# Sheet4.net
KiCad netlist of a schematic drawn in Altium Designer
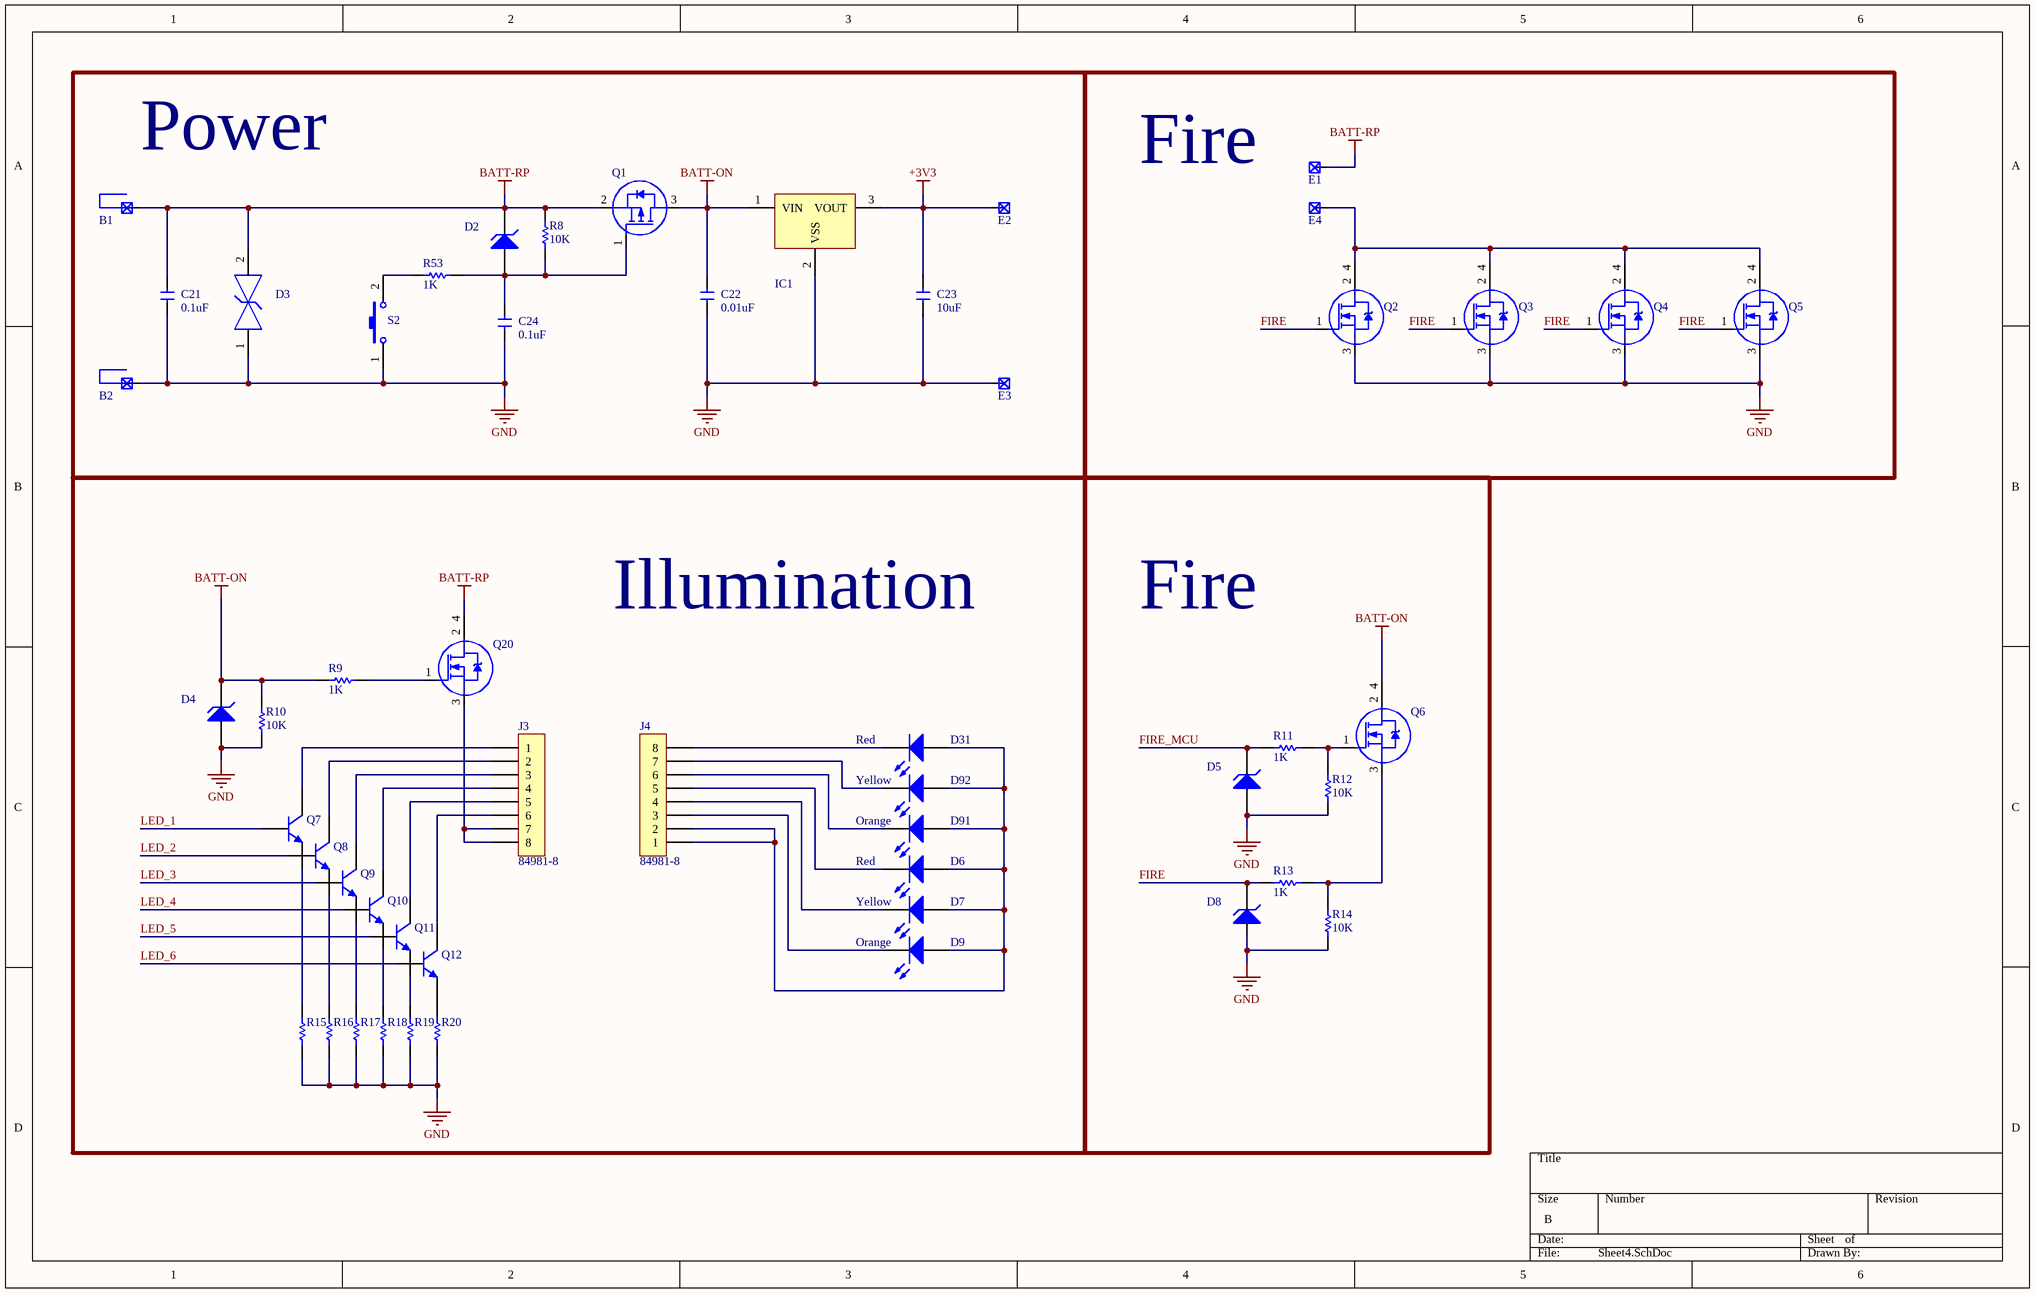
[diagram p0: Sheet4.SchDoc]

(export (version "E")
  (design (tool "Eeschema 10.0.6"))
  (components
    (comp (ref "B1")
      (value "BATT CONTACT")
      (footprint "BATTERY CONTACT KEYSTONE 209")
      (description "BATT_Contact_Keystone_209")
      (fields (field (name "MANUFACTURER") "Keystone Electronics"))
      (libsource (lib "Erico_Ignitor") (part "BATT_Contact_Keystone_209"))
    )
    (comp (ref "B2")
      (value "BATT CONTACT")
      (footprint "BATTERY CONTACT KEYSTONE 209")
      (description "BATT_Contact_Keystone_209")
      (fields (field (name "MANUFACTURER") "Keystone Electronics"))
      (libsource (lib "Erico_Ignitor") (part "BATT_Contact_Keystone_209"))
    )
    (comp (ref "C21")
      (value "0.1uF")
      (footprint "CAPC2012N")
      (description "CAP CER 0.1UF 50V")
      (fields (field (name "MANUFACTURER") "KEMET") (field (name "TOLERANCE") "20%"))
      (libsource (lib "Erico_Ignitor") (part "Cap_0.1uF_50V_0805"))
    )
    (comp (ref "C22")
      (value "0.01uF")
      (footprint "CAPC2012N")
      (description "CAP CER 0.01UF 50V")
      (fields (field (name "MANUFACTURER") "KEMET") (field (name "TOLERANCE") "10%"))
      (libsource (lib "Erico_Ignitor") (part "Cap_0.01uF_50V_0805"))
    )
    (comp (ref "C23")
      (value "10uF")
      (footprint "CAPC2012N")
      (description "CAP CER 10uF 10V 0805")
      (fields (field (name "MANUFACTURER") "TDK") (field (name "TOLERANCE") "10%"))
      (libsource (lib "Erico_Ignitor") (part "Cap_10uF_10V_0805"))
    )
    (comp (ref "C24")
      (value "0.1uF")
      (footprint "CAPC2012N")
      (description "CAP CER 0.1UF 50V")
      (fields (field (name "MANUFACTURER") "KEMET") (field (name "TOLERANCE") "20%"))
      (libsource (lib "Erico_Ignitor") (part "Cap_0.1uF_50V_0805"))
    )
    (comp (ref "D2")
      (value "Diode, Zener, BZX84C18")
      (footprint "SOT23")
      (description "DIODE ZENER 18V 300mW SOT23")
      (fields (field (name "MANUFACTURER") "Diodes") (field (name "TOLERANCE") "6%"))
      (libsource (lib "Erico_Ignitor") (part "Diode_BZX84C18"))
    )
    (comp (ref "D3")
      (value "SMAJ24CA")
      (footprint "FP-SMAJ-CA-MFG")
      (description "TVS DIODE 24V 38.9V DO214AC")
      (fields
        (field (name "MANUFACTURER") "Littelfuse")
        (field (name "OCTOPART") "https://octopart.com/smaj24ca-littelfuse-350011")
      )
      (libsource (lib "Altium Content Vault") (part "876f4347bf90aa6f500f43e3cd03972"))
    )
    (comp (ref "D4")
      (value "Diode, Zener, BZX84C18")
      (footprint "SOT23")
      (description "DIODE ZENER 18V 300mW SOT23")
      (fields (field (name "MANUFACTURER") "Diodes") (field (name "TOLERANCE") "6%"))
      (libsource (lib "Erico_Ignitor") (part "Diode_BZX84C18"))
    )
    (comp (ref "D5")
      (value "Diode, Zener, BZX84C18")
      (footprint "SOT23")
      (description "DIODE ZENER 18V 300mW SOT23")
      (fields (field (name "MANUFACTURER") "Diodes") (field (name "TOLERANCE") "6%"))
      (libsource (lib "Erico_Ignitor") (part "Diode_BZX84C18"))
    )
    (comp (ref "D6")
      (value "LED_RED_0603")
      (footprint "LED_LTST-C190KRKT")
      (description "LED RED 0603 SMD")
      (fields (field (name "MANUFACTURER") "Vishay Lite-On"))
      (libsource (lib "Erico_Ignitor") (part "LED_RED_LTST-C190"))
    )
    (comp (ref "D7")
      (value "LED_YELLOW_LTST-C194KSKT")
      (footprint "LED_LTST-C194KSKT")
      (description "LED YELLOW 0603 SMD")
      (fields (field (name "MANUFACTURER") "Vishay Lite-On"))
      (libsource (lib "Erico_Ignitor") (part "LED_YELLOW_LTST-C194KSKT"))
    )
    (comp (ref "D8")
      (value "Diode, Zener, BZX84C18")
      (footprint "SOT23")
      (description "DIODE ZENER 18V 300mW SOT23")
      (fields (field (name "MANUFACTURER") "Diodes") (field (name "TOLERANCE") "6%"))
      (libsource (lib "Erico_Ignitor") (part "Diode_BZX84C18"))
    )
    (comp (ref "D9")
      (value "LED_ORANGE_0603")
      (footprint "LED_LTST-C190KFKT")
      (description "LED ORANGE 0603 SMD")
      (fields (field (name "MANUFACTURER") "Vishay Lite-On"))
      (libsource (lib "Erico_Ignitor") (part "LED_ORANGE_LTST-C190KFKT"))
    )
    (comp (ref "D31")
      (value "LED_RED_0603")
      (footprint "LED_LTST-C190KRKT")
      (description "LED RED 0603 SMD")
      (fields (field (name "MANUFACTURER") "Vishay Lite-On"))
      (libsource (lib "Erico_Ignitor") (part "LED_RED_LTST-C190"))
    )
    (comp (ref "D91")
      (value "LED_ORANGE_0603")
      (footprint "LED_LTST-C190KFKT")
      (description "LED ORANGE 0603 SMD")
      (fields (field (name "MANUFACTURER") "Vishay Lite-On"))
      (libsource (lib "Erico_Ignitor") (part "LED_ORANGE_LTST-C190KFKT"))
    )
    (comp (ref "D92")
      (value "LED_YELLOW_LTST-C194KSKT")
      (footprint "LED_LTST-C194KSKT")
      (description "LED YELLOW 0603 SMD")
      (fields (field (name "MANUFACTURER") "Vishay Lite-On"))
      (libsource (lib "Erico_Ignitor") (part "LED_YELLOW_LTST-C194KSKT"))
    )
    (comp (ref "E1")
      (value "Testpoint")
      (footprint "Test_point")
      (libsource (lib "Erico_Ignitor") (part "Test Point"))
    )
    (comp (ref "E2") (value "Testpoint") (footprint "Test_point") (libsource (lib "") (part "Test Point_1")))
    (comp (ref "E3") (value "Testpoint") (footprint "Test_point") (libsource (lib "") (part "Test Point_1")))
    (comp (ref "E4")
      (value "Testpoint")
      (footprint "Test_point")
      (libsource (lib "Erico_Ignitor") (part "Test Point"))
    )
    (comp (ref "IC1")
      (value "LP2950")
      (footprint "DPAK-369C")
      (description "Voltage Regulator")
      (fields (field (name "MANUFACTURER") "ON Semiconductor"))
      (libsource (lib "Erico_Ignitor") (part "LP2950"))
    )
    (comp (ref "J3") (value "84981-8") (footprint "84981-8") (libsource (lib "") (part "84981-8_1")))
    (comp (ref "J4")
      (value "84981-8")
      (footprint "84981-8")
      (libsource (lib "Erico_Ignitor") (part "84981-8"))
    )
    (comp (ref "Q1")
      (value "BSS84LT1G")
      (footprint "SOT23")
      (description "MOSFET P-CH 50V 130mA SOT-23")
      (fields (field (name "MANUFACTURER") "ON Semiconductor"))
      (libsource (lib "Erico_Ignitor") (part "BSS84LT1G"))
    )
    (comp (ref "Q2")
      (value "QD2PAK")
      (footprint "D2PAK")
      (description "MOSFET N-CH 55V 53A D2PAK")
      (libsource (lib "SchLibrary") (part "IRFZ46NSTRL"))
    )
    (comp (ref "Q3")
      (value "QD2PAK")
      (footprint "D2PAK")
      (description "MOSFET N-CH 55V 53A D2PAK")
      (libsource (lib "SchLibrary") (part "IRFZ46NSTRL"))
    )
    (comp (ref "Q4")
      (value "QD2PAK")
      (footprint "D2PAK")
      (description "MOSFET N-CH 55V 53A D2PAK")
      (libsource (lib "SchLibrary") (part "IRFZ46NSTRL"))
    )
    (comp (ref "Q5")
      (value "QD2PAK")
      (footprint "D2PAK")
      (description "MOSFET N-CH 55V 53A D2PAK")
      (libsource (lib "SchLibrary") (part "IRFZ46NSTRL"))
    )
    (comp (ref "Q6")
      (value "FQT7N10LTF")
      (footprint "SOT223-4N")
      (description "MOSFET N-CH 30V 0.8A SOT416")
      (fields (field (name "MANUFACTURER") "ON Semiconductor / Fairchild"))
      (libsource (lib "Erico_Ignitor") (part "FET_N-Chan_SOT-223"))
    )
    (comp (ref "Q7")
      (value "BC846B")
      (footprint "SOT23")
      (description "TRAN NPN 100MA 65V")
      (fields (field (name "MANUFACTURER") "NXP Semiconductors"))
      (libsource (lib "Erico_Ignitor") (part "BC846B"))
    )
    (comp (ref "Q8")
      (value "BC846B")
      (footprint "SOT23")
      (description "TRAN NPN 100MA 65V")
      (fields (field (name "MANUFACTURER") "NXP Semiconductors"))
      (libsource (lib "Erico_Ignitor") (part "BC846B"))
    )
    (comp (ref "Q9")
      (value "BC846B")
      (footprint "SOT23")
      (description "TRAN NPN 100MA 65V")
      (fields (field (name "MANUFACTURER") "NXP Semiconductors"))
      (libsource (lib "Erico_Ignitor") (part "BC846B"))
    )
    (comp (ref "Q10")
      (value "BC846B")
      (footprint "SOT23")
      (description "TRAN NPN 100MA 65V")
      (fields (field (name "MANUFACTURER") "NXP Semiconductors"))
      (libsource (lib "Erico_Ignitor") (part "BC846B"))
    )
    (comp (ref "Q11")
      (value "BC846B")
      (footprint "SOT23")
      (description "TRAN NPN 100MA 65V")
      (fields (field (name "MANUFACTURER") "NXP Semiconductors"))
      (libsource (lib "Erico_Ignitor") (part "BC846B"))
    )
    (comp (ref "Q12")
      (value "BC846B")
      (footprint "SOT23")
      (description "TRAN NPN 100MA 65V")
      (fields (field (name "MANUFACTURER") "NXP Semiconductors"))
      (libsource (lib "Erico_Ignitor") (part "BC846B"))
    )
    (comp (ref "Q20")
      (value "FQT7N10LTF")
      (footprint "SOT223-4N")
      (description "MOSFET N-CH 30V 0.8A SOT416")
      (fields (field (name "MANUFACTURER") "ON Semiconductor / Fairchild"))
      (libsource (lib "Erico_Ignitor") (part "FET_N-Chan_SOT-223"))
    )
    (comp (ref "R8")
      (value "10K")
      (footprint "RESC2012N")
      (description "RES 10K OHM 1/8W 1% 0805")
      (fields (field (name "MANUFACTURER") "Vishay") (field (name "TOLERANCE") "1%"))
      (libsource (lib "Erico_Ignitor") (part "Res_10K_0805"))
    )
    (comp (ref "R9")
      (value "Res_1.0K_0805")
      (footprint "RESC2012N")
      (description "RES 1.0K OHM 1/8W 1% 0805")
      (fields
        (field (name "MANUFACTURER") "Yageo")
        (field (name "TOLERANCE") "±1%")
        (field (name "RESISTANCE (OHMS)") "1K")
      )
      (libsource (lib "Erico_Ignitor") (part "Res_1.0K_0805"))
    )
    (comp (ref "R10")
      (value "10K")
      (footprint "RESC2012N")
      (description "RES 10K OHM 1/8W 1% 0805")
      (fields (field (name "MANUFACTURER") "Vishay") (field (name "TOLERANCE") "1%"))
      (libsource (lib "Erico_Ignitor") (part "Res_10K_0805"))
    )
    (comp (ref "R11")
      (value "Res_1.0K_0805")
      (footprint "RESC2012N")
      (description "RES 1.0K OHM 1/8W 1% 0805")
      (fields
        (field (name "MANUFACTURER") "Yageo")
        (field (name "TOLERANCE") "±1%")
        (field (name "RESISTANCE (OHMS)") "1K")
      )
      (libsource (lib "Erico_Ignitor") (part "Res_1.0K_0805"))
    )
    (comp (ref "R12")
      (value "10K")
      (footprint "RESC2012N")
      (description "RES 10K OHM 1/8W 1% 0805")
      (fields (field (name "MANUFACTURER") "Vishay") (field (name "TOLERANCE") "1%"))
      (libsource (lib "Erico_Ignitor") (part "Res_10K_0805"))
    )
    (comp (ref "R13")
      (value "Res_1.0K_0805")
      (footprint "RESC2012N")
      (description "RES 1.0K OHM 1/8W 1% 0805")
      (fields
        (field (name "MANUFACTURER") "Yageo")
        (field (name "TOLERANCE") "±1%")
        (field (name "RESISTANCE (OHMS)") "1K")
      )
      (libsource (lib "Erico_Ignitor") (part "Res_1.0K_0805"))
    )
    (comp (ref "R14")
      (value "10K")
      (footprint "RESC2012N")
      (description "RES 10K OHM 1/8W 1% 0805")
      (fields (field (name "MANUFACTURER") "Vishay") (field (name "TOLERANCE") "1%"))
      (libsource (lib "Erico_Ignitor") (part "Res_10K_0805"))
    )
    (comp (ref "R15")
      (value "150")
      (footprint "RESC2012N")
      (description "RES 150 OHM 1/8W 1% 0805")
      (fields (field (name "MANUFACTURER") "Vishay") (field (name "TOLERANCE") "1%"))
      (libsource (lib "Erico_Ignitor") (part "Res_150_0805"))
    )
    (comp (ref "R16")
      (value "150")
      (footprint "RESC2012N")
      (description "RES 150 OHM 1/8W 1% 0805")
      (fields (field (name "MANUFACTURER") "Vishay") (field (name "TOLERANCE") "1%"))
      (libsource (lib "Erico_Ignitor") (part "Res_150_0805"))
    )
    (comp (ref "R17")
      (value "150")
      (footprint "RESC2012N")
      (description "RES 150 OHM 1/8W 1% 0805")
      (fields (field (name "MANUFACTURER") "Vishay") (field (name "TOLERANCE") "1%"))
      (libsource (lib "Erico_Ignitor") (part "Res_150_0805"))
    )
    (comp (ref "R18")
      (value "150")
      (footprint "RESC2012N")
      (description "RES 150 OHM 1/8W 1% 0805")
      (fields (field (name "MANUFACTURER") "Vishay") (field (name "TOLERANCE") "1%"))
      (libsource (lib "Erico_Ignitor") (part "Res_150_0805"))
    )
    (comp (ref "R19")
      (value "150")
      (footprint "RESC2012N")
      (description "RES 150 OHM 1/8W 1% 0805")
      (fields (field (name "MANUFACTURER") "Vishay") (field (name "TOLERANCE") "1%"))
      (libsource (lib "Erico_Ignitor") (part "Res_150_0805"))
    )
    (comp (ref "R20")
      (value "150")
      (footprint "RESC2012N")
      (description "RES 150 OHM 1/8W 1% 0805")
      (fields (field (name "MANUFACTURER") "Vishay") (field (name "TOLERANCE") "1%"))
      (libsource (lib "Erico_Ignitor") (part "Res_150_0805"))
    )
    (comp (ref "R53")
      (value "Res_1.0K_0805")
      (footprint "RESC2012N")
      (description "RES 1.0K OHM 1/8W 1% 0805")
      (fields
        (field (name "MANUFACTURER") "Yageo")
        (field (name "TOLERANCE") "±1%")
        (field (name "RESISTANCE (OHMS)") "1K")
      )
      (libsource (lib "Erico_Ignitor") (part "Res_1.0K_0805"))
    )
    (comp (ref "S2")
      (value "SW_MX1A")
      (footprint "SW_CHERRY_MX1A-21NW")
      (description "SWITCH PUSH BUTTON")
      (fields (field (name "MANUFACTURER") "Cherry"))
      (libsource (lib "Erico_Ignitor") (part "SW_MX1A"))
    )
  )
  (nets
    (net (code "1") (name "+3V3") (class "Default")
      (node (ref "C23") (pin "2") (pinfunction "2_2") (pintype "passive"))
      (node (ref "E2") (pin "1") (pinfunction "Test_1") (pintype "passive"))
      (node (ref "IC1") (pin "3") (pinfunction "VOUT_3") (pintype "power_in"))
    )
    (net (code "2") (name "/FIRE") (class "Default")
      (node (ref "D8") (pin "3") (pinfunction "K_3") (pintype "passive"))
      (node (ref "Q2") (pin "1") (pinfunction "G_1") (pintype "passive"))
      (node (ref "Q3") (pin "1") (pinfunction "G_1") (pintype "passive"))
      (node (ref "Q4") (pin "1") (pinfunction "G_1") (pintype "passive"))
      (node (ref "Q5") (pin "1") (pinfunction "G_1") (pintype "passive"))
      (node (ref "R13") (pin "2") (pinfunction "2_2") (pintype "passive"))
    )
    (net (code "3") (name "/FIRE_MCU") (class "Default")
      (node (ref "D5") (pin "3") (pinfunction "K_3") (pintype "passive"))
      (node (ref "R11") (pin "2") (pinfunction "2_2") (pintype "passive"))
    )
    (net (code "4") (name "/LED_1") (class "Default")
      (node (ref "Q7") (pin "1") (pinfunction "B_1") (pintype "passive"))
    )
    (net (code "5") (name "/LED_2") (class "Default")
      (node (ref "Q8") (pin "1") (pinfunction "B_1") (pintype "passive"))
    )
    (net (code "6") (name "/LED_3") (class "Default")
      (node (ref "Q9") (pin "1") (pinfunction "B_1") (pintype "passive"))
    )
    (net (code "7") (name "/LED_4") (class "Default")
      (node (ref "Q10") (pin "1") (pinfunction "B_1") (pintype "passive"))
    )
    (net (code "8") (name "/LED_5") (class "Default")
      (node (ref "Q11") (pin "1") (pinfunction "B_1") (pintype "passive"))
    )
    (net (code "9") (name "/LED_6") (class "Default")
      (node (ref "Q12") (pin "1") (pinfunction "B_1") (pintype "passive"))
    )
    (net (code "10") (name "BATT-ON") (class "Default")
      (node (ref "C22") (pin "2") (pinfunction "2_2") (pintype "passive"))
      (node (ref "D4") (pin "3") (pinfunction "K_3") (pintype "passive"))
      (node (ref "IC1") (pin "1") (pinfunction "VIN_1") (pintype "passive"))
      (node (ref "Q1") (pin "3") (pinfunction "3_3") (pintype "passive"))
      (node (ref "Q6") (pin "4") (pinfunction "D_4") (pintype "passive"))
      (node (ref "R10") (pin "2") (pinfunction "2_2") (pintype "passive"))
      (node (ref "R9") (pin "2") (pinfunction "2_2") (pintype "passive"))
    )
    (net (code "11") (name "BATT-RP") (class "Default")
      (node (ref "B1") (pin "1") (pinfunction "Test_1") (pintype "passive"))
      (node (ref "C21") (pin "2") (pinfunction "2_2") (pintype "passive"))
      (node (ref "D2") (pin "3") (pinfunction "K_3") (pintype "passive"))
      (node (ref "D3") (pin "2") (pinfunction "2_2") (pintype "passive"))
      (node (ref "E1") (pin "1") (pinfunction "Test_1") (pintype "passive"))
      (node (ref "Q1") (pin "2") (pinfunction "2_2") (pintype "passive"))
      (node (ref "Q20") (pin "4") (pinfunction "D_4") (pintype "passive"))
      (node (ref "R8") (pin "2") (pinfunction "2_2") (pintype "passive"))
    )
    (net (code "12") (name "GND") (class "Default")
      (node (ref "B2") (pin "1") (pinfunction "Test_1") (pintype "passive"))
      (node (ref "C21") (pin "1") (pinfunction "1_1") (pintype "passive"))
      (node (ref "C22") (pin "1") (pinfunction "1_1") (pintype "passive"))
      (node (ref "C23") (pin "1") (pinfunction "1_1") (pintype "passive"))
      (node (ref "C24") (pin "1") (pinfunction "1_1") (pintype "passive"))
      (node (ref "D3") (pin "1") (pinfunction "1_1") (pintype "passive"))
      (node (ref "D4") (pin "1") (pinfunction "A_1") (pintype "passive"))
      (node (ref "D5") (pin "1") (pinfunction "A_1") (pintype "passive"))
      (node (ref "D8") (pin "1") (pinfunction "A_1") (pintype "passive"))
      (node (ref "E3") (pin "1") (pinfunction "Test_1") (pintype "passive"))
      (node (ref "IC1") (pin "2") (pinfunction "VSS_2") (pintype "power_in"))
      (node (ref "Q2") (pin "3") (pinfunction "S_3") (pintype "passive"))
      (node (ref "Q3") (pin "3") (pinfunction "S_3") (pintype "passive"))
      (node (ref "Q4") (pin "3") (pinfunction "S_3") (pintype "passive"))
      (node (ref "Q5") (pin "3") (pinfunction "S_3") (pintype "passive"))
      (node (ref "R10") (pin "1") (pinfunction "1_1") (pintype "passive"))
      (node (ref "R12") (pin "1") (pinfunction "1_1") (pintype "passive"))
      (node (ref "R14") (pin "1") (pinfunction "1_1") (pintype "passive"))
      (node (ref "R15") (pin "1") (pinfunction "1_1") (pintype "passive"))
      (node (ref "R16") (pin "1") (pinfunction "1_1") (pintype "passive"))
      (node (ref "R17") (pin "1") (pinfunction "1_1") (pintype "passive"))
      (node (ref "R18") (pin "1") (pinfunction "1_1") (pintype "passive"))
      (node (ref "R19") (pin "1") (pinfunction "1_1") (pintype "passive"))
      (node (ref "R20") (pin "1") (pinfunction "1_1") (pintype "passive"))
      (node (ref "S2") (pin "1") (pinfunction "1_1") (pintype "passive"))
    )
    (net (code "13") (name "Net-(D2-A)") (class "Default")
      (node (ref "C24") (pin "2") (pinfunction "2_2") (pintype "passive"))
      (node (ref "D2") (pin "1") (pinfunction "A_1") (pintype "passive"))
      (node (ref "Q1") (pin "1") (pinfunction "1_1") (pintype "passive"))
      (node (ref "R53") (pin "1") (pinfunction "1_1") (pintype "passive"))
      (node (ref "R8") (pin "1") (pinfunction "1_1") (pintype "passive"))
    )
    (net (code "14") (name "Net-(D6-Pad1)") (class "Default")
      (node (ref "D6") (pin "1") (pinfunction "1_1") (pintype "passive"))
      (node (ref "J4") (pin "5") (pinfunction "5_5") (pintype "passive"))
    )
    (net (code "15") (name "Net-(D7-Pad1)") (class "Default")
      (node (ref "D7") (pin "1") (pinfunction "1_1") (pintype "passive"))
      (node (ref "J4") (pin "4") (pinfunction "4_4") (pintype "passive"))
    )
    (net (code "16") (name "Net-(D9-Pad1)") (class "Default")
      (node (ref "D9") (pin "1") (pinfunction "1_1") (pintype "passive"))
      (node (ref "J4") (pin "3") (pinfunction "3_3") (pintype "passive"))
    )
    (net (code "17") (name "Net-(D31-Pad1)") (class "Default")
      (node (ref "D31") (pin "1") (pinfunction "1_1") (pintype "passive"))
      (node (ref "J4") (pin "8") (pinfunction "8_8") (pintype "passive"))
    )
    (net (code "18") (name "Net-(D31-Pad2)") (class "Default")
      (node (ref "D31") (pin "2") (pinfunction "2_2") (pintype "passive"))
      (node (ref "D6") (pin "2") (pinfunction "2_2") (pintype "passive"))
      (node (ref "D7") (pin "2") (pinfunction "2_2") (pintype "passive"))
      (node (ref "D9") (pin "2") (pinfunction "2_2") (pintype "passive"))
      (node (ref "D91") (pin "2") (pinfunction "2_2") (pintype "passive"))
      (node (ref "D92") (pin "2") (pinfunction "2_2") (pintype "passive"))
      (node (ref "J4") (pin "1") (pinfunction "1_1") (pintype "passive"))
      (node (ref "J4") (pin "2") (pinfunction "2_2") (pintype "passive"))
    )
    (net (code "19") (name "Net-(D91-Pad1)") (class "Default")
      (node (ref "D91") (pin "1") (pinfunction "1_1") (pintype "passive"))
      (node (ref "J4") (pin "6") (pinfunction "6_6") (pintype "passive"))
    )
    (net (code "20") (name "Net-(D92-Pad1)") (class "Default")
      (node (ref "D92") (pin "1") (pinfunction "1_1") (pintype "passive"))
      (node (ref "J4") (pin "7") (pinfunction "7_7") (pintype "passive"))
    )
    (net (code "21") (name "Net-(E4-Test)") (class "Default")
      (node (ref "E4") (pin "1") (pinfunction "Test_1") (pintype "passive"))
      (node (ref "Q2") (pin "4") (pinfunction "D_4") (pintype "passive"))
      (node (ref "Q3") (pin "4") (pinfunction "D_4") (pintype "passive"))
      (node (ref "Q4") (pin "4") (pinfunction "D_4") (pintype "passive"))
      (node (ref "Q5") (pin "4") (pinfunction "D_4") (pintype "passive"))
    )
    (net (code "22") (name "Net-(Q6-G)") (class "Default")
      (node (ref "Q6") (pin "1") (pinfunction "G_1") (pintype "passive"))
      (node (ref "R11") (pin "1") (pinfunction "1_1") (pintype "passive"))
      (node (ref "R12") (pin "2") (pinfunction "2_2") (pintype "passive"))
    )
    (net (code "23") (name "Net-(Q6-S)") (class "Default")
      (node (ref "Q6") (pin "3") (pinfunction "S_3") (pintype "passive"))
      (node (ref "R13") (pin "1") (pinfunction "1_1") (pintype "passive"))
      (node (ref "R14") (pin "2") (pinfunction "2_2") (pintype "passive"))
    )
    (net (code "24") (name "Net-(Q7-C)") (class "Default")
      (node (ref "J3") (pin "1") (pinfunction "1_1") (pintype "passive"))
      (node (ref "Q7") (pin "3") (pinfunction "C_3") (pintype "passive"))
    )
    (net (code "25") (name "Net-(Q7-E)") (class "Default")
      (node (ref "Q7") (pin "2") (pinfunction "E_2") (pintype "passive"))
      (node (ref "R15") (pin "2") (pinfunction "2_2") (pintype "passive"))
    )
    (net (code "26") (name "Net-(Q8-C)") (class "Default")
      (node (ref "J3") (pin "2") (pinfunction "2_2") (pintype "passive"))
      (node (ref "Q8") (pin "3") (pinfunction "C_3") (pintype "passive"))
    )
    (net (code "27") (name "Net-(Q8-E)") (class "Default")
      (node (ref "Q8") (pin "2") (pinfunction "E_2") (pintype "passive"))
      (node (ref "R16") (pin "2") (pinfunction "2_2") (pintype "passive"))
    )
    (net (code "28") (name "Net-(Q9-C)") (class "Default")
      (node (ref "J3") (pin "3") (pinfunction "3_3") (pintype "passive"))
      (node (ref "Q9") (pin "3") (pinfunction "C_3") (pintype "passive"))
    )
    (net (code "29") (name "Net-(Q9-E)") (class "Default")
      (node (ref "Q9") (pin "2") (pinfunction "E_2") (pintype "passive"))
      (node (ref "R17") (pin "2") (pinfunction "2_2") (pintype "passive"))
    )
    (net (code "30") (name "Net-(Q10-C)") (class "Default")
      (node (ref "J3") (pin "4") (pinfunction "4_4") (pintype "passive"))
      (node (ref "Q10") (pin "3") (pinfunction "C_3") (pintype "passive"))
    )
    (net (code "31") (name "Net-(Q10-E)") (class "Default")
      (node (ref "Q10") (pin "2") (pinfunction "E_2") (pintype "passive"))
      (node (ref "R18") (pin "2") (pinfunction "2_2") (pintype "passive"))
    )
    (net (code "32") (name "Net-(Q11-C)") (class "Default")
      (node (ref "J3") (pin "5") (pinfunction "5_5") (pintype "passive"))
      (node (ref "Q11") (pin "3") (pinfunction "C_3") (pintype "passive"))
    )
    (net (code "33") (name "Net-(Q11-E)") (class "Default")
      (node (ref "Q11") (pin "2") (pinfunction "E_2") (pintype "passive"))
      (node (ref "R19") (pin "2") (pinfunction "2_2") (pintype "passive"))
    )
    (net (code "34") (name "Net-(Q12-C)") (class "Default")
      (node (ref "J3") (pin "6") (pinfunction "6_6") (pintype "passive"))
      (node (ref "Q12") (pin "3") (pinfunction "C_3") (pintype "passive"))
    )
    (net (code "35") (name "Net-(Q12-E)") (class "Default")
      (node (ref "Q12") (pin "2") (pinfunction "E_2") (pintype "passive"))
      (node (ref "R20") (pin "2") (pinfunction "2_2") (pintype "passive"))
    )
    (net (code "36") (name "Net-(Q20-G)") (class "Default")
      (node (ref "Q20") (pin "1") (pinfunction "G_1") (pintype "passive"))
      (node (ref "R9") (pin "1") (pinfunction "1_1") (pintype "passive"))
    )
    (net (code "37") (name "Net-(Q20-S)") (class "Default")
      (node (ref "J3") (pin "7") (pinfunction "7_7") (pintype "passive"))
      (node (ref "J3") (pin "8") (pinfunction "8_8") (pintype "passive"))
      (node (ref "Q20") (pin "3") (pinfunction "S_3") (pintype "passive"))
    )
    (net (code "38") (name "Net-(R53-Pad2)") (class "Default")
      (node (ref "R53") (pin "2") (pinfunction "2_2") (pintype "passive"))
      (node (ref "S2") (pin "2") (pinfunction "2_2") (pintype "passive"))
    )
    (net (code "39") (name "unconnected-(Q2-D-Pad2)") (class "Default")
      (node (ref "Q2") (pin "2") (pinfunction "D_2") (pintype "passive"))
    )
    (net (code "40") (name "unconnected-(Q3-D-Pad2)") (class "Default")
      (node (ref "Q3") (pin "2") (pinfunction "D_2") (pintype "passive"))
    )
    (net (code "41") (name "unconnected-(Q4-D-Pad2)") (class "Default")
      (node (ref "Q4") (pin "2") (pinfunction "D_2") (pintype "passive"))
    )
    (net (code "42") (name "unconnected-(Q5-D-Pad2)") (class "Default")
      (node (ref "Q5") (pin "2") (pinfunction "D_2") (pintype "passive"))
    )
    (net (code "43") (name "unconnected-(Q6-D-Pad2)") (class "Default")
      (node (ref "Q6") (pin "2") (pinfunction "D_2") (pintype "passive"))
    )
    (net (code "44") (name "unconnected-(Q20-D-Pad2)") (class "Default")
      (node (ref "Q20") (pin "2") (pinfunction "D_2") (pintype "passive"))
    )
  )
)
